# 01_-_MCU.net
KiCad netlist of a schematic drawn in Altium Designer
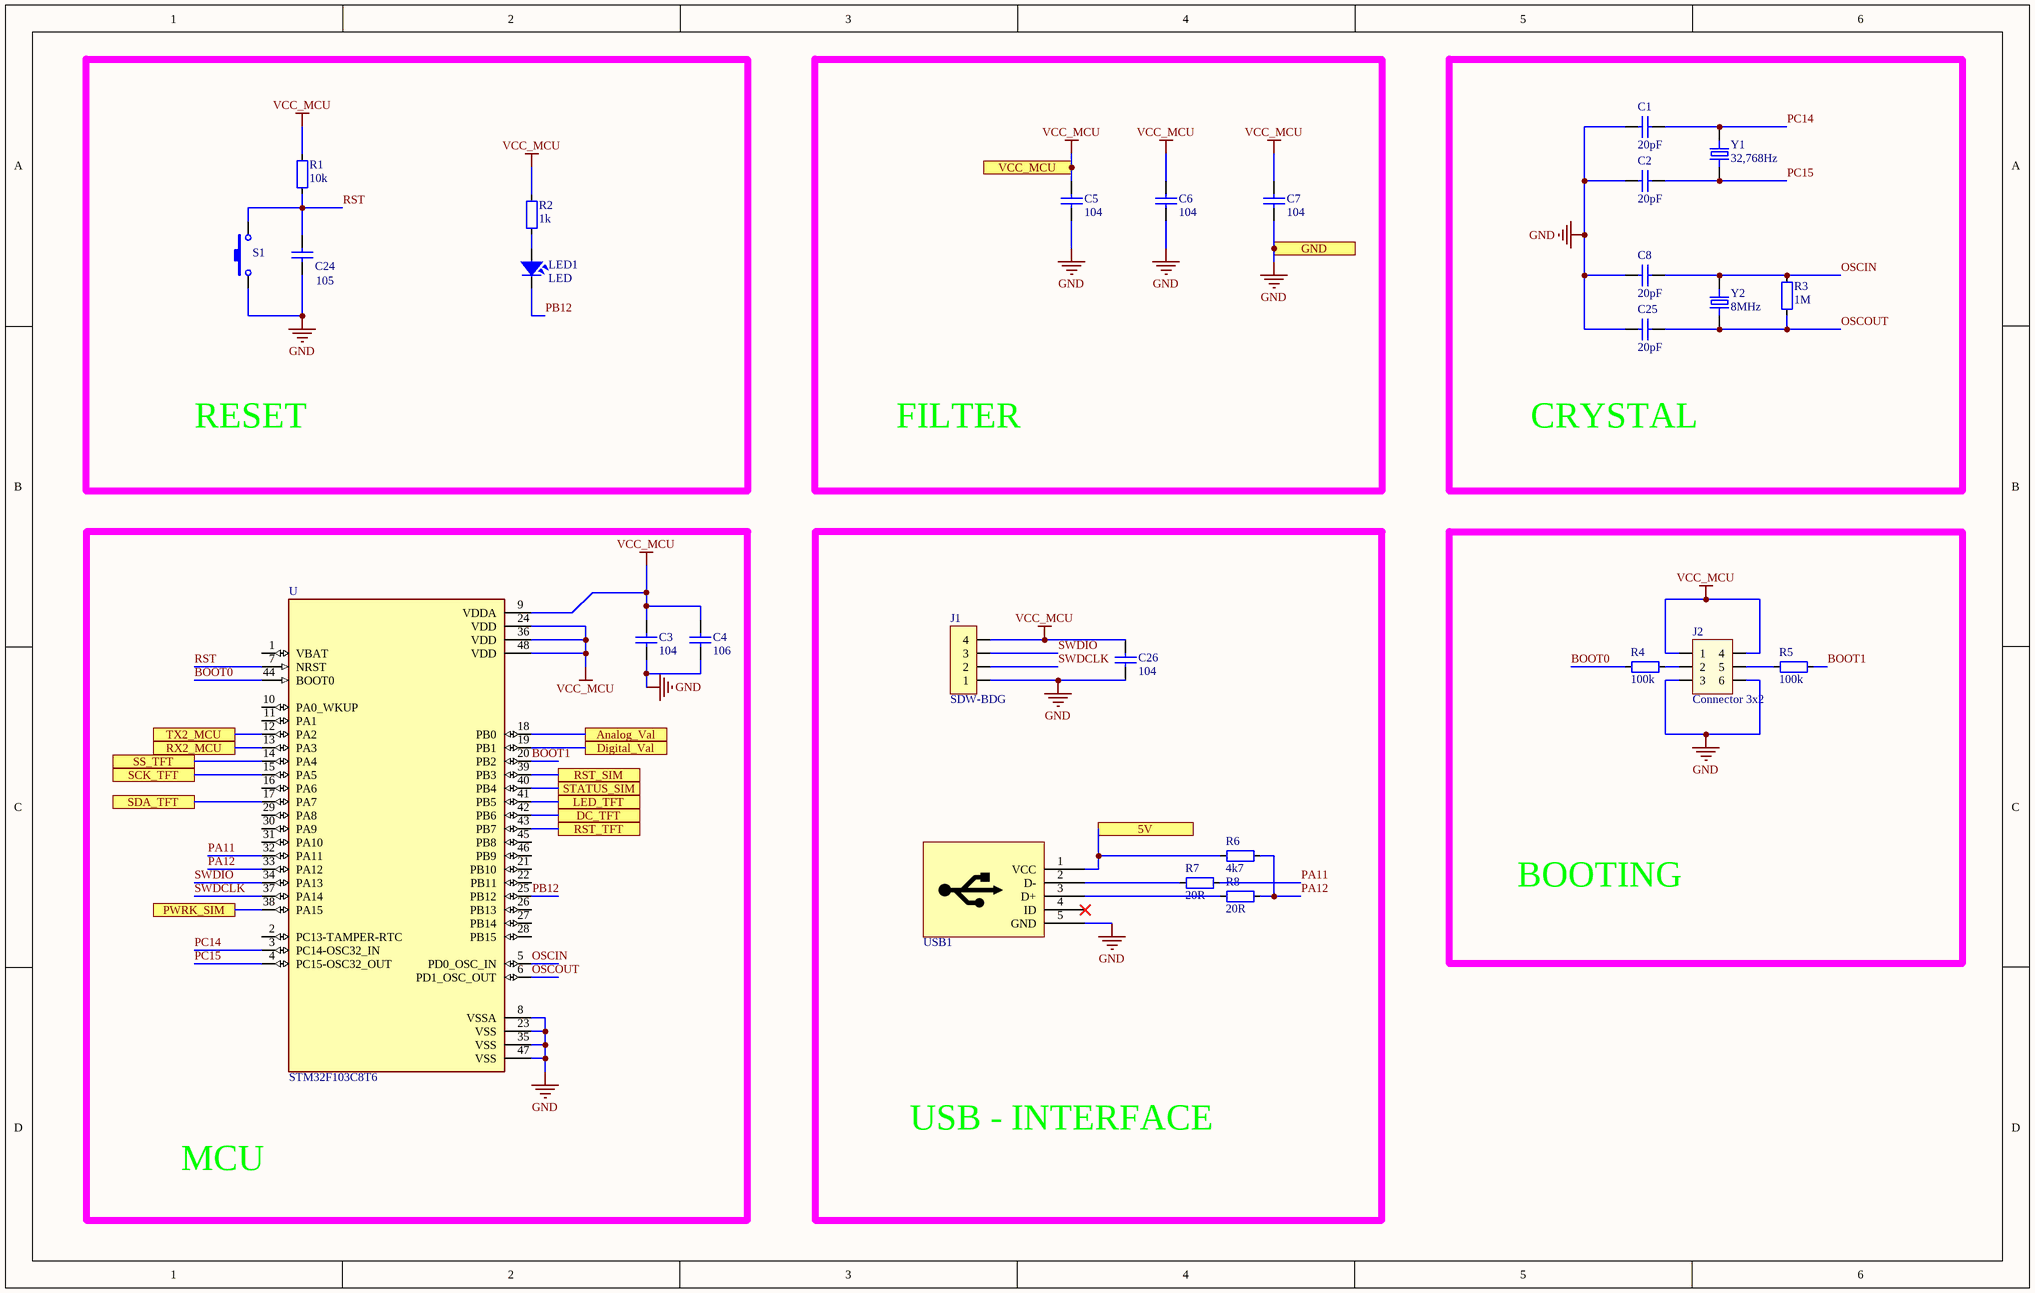
[diagram p0: [01] - MCU.SchDoc]

(export (version "E")
  (design (tool "Eeschema 10.0.6"))
  (components
    (comp (ref "C1")
      (value "20pF")
      (footprint "CAP_0805")
      (description "Capacitor")
      (fields (field (name "PUBLISHER") "Altium Limited"))
      (libsource (lib "HS_Lib") (part "CapSMD"))
    )
    (comp (ref "C2")
      (value "20pF")
      (footprint "CAP_0805")
      (description "Capacitor")
      (fields (field (name "PUBLISHER") "Altium Limited"))
      (libsource (lib "HS_Lib") (part "CapSMD"))
    )
    (comp (ref "C3")
      (value "104")
      (footprint "CAP_0603")
      (description "Capacitor")
      (fields (field (name "PUBLISHER") "Altium Limited"))
      (libsource (lib "HS_Lib") (part "CapSMD"))
    )
    (comp (ref "C4")
      (value "106")
      (footprint "CAP_1206")
      (description "Capacitor")
      (fields (field (name "PUBLISHER") "Altium Limited"))
      (libsource (lib "HS_Lib") (part "CapSMD"))
    )
    (comp (ref "C5")
      (value "104")
      (footprint "CAP_0603")
      (description "Capacitor")
      (fields (field (name "PUBLISHER") "Altium Limited"))
      (libsource (lib "HS_Lib") (part "CapSMD"))
    )
    (comp (ref "C6")
      (value "104")
      (footprint "CAP_0603")
      (description "Capacitor")
      (fields (field (name "PUBLISHER") "Altium Limited"))
      (libsource (lib "HS_Lib") (part "CapSMD"))
    )
    (comp (ref "C7")
      (value "104")
      (footprint "CAP_0603")
      (description "Capacitor")
      (fields (field (name "PUBLISHER") "Altium Limited"))
      (libsource (lib "HS_Lib") (part "CapSMD"))
    )
    (comp (ref "C8")
      (value "20pF")
      (footprint "CAP_0805")
      (description "Capacitor")
      (fields (field (name "PUBLISHER") "Altium Limited"))
      (libsource (lib "HS_Lib") (part "CapSMD"))
    )
    (comp (ref "C24")
      (value "105")
      (footprint "CAP_0603")
      (description "Capacitor")
      (fields (field (name "PUBLISHER") "Altium Limited"))
      (libsource (lib "HS_Lib") (part "CapSMD"))
    )
    (comp (ref "C25")
      (value "20pF")
      (footprint "CAP_0805")
      (description "Capacitor")
      (fields (field (name "PUBLISHER") "Altium Limited"))
      (libsource (lib "HS_Lib") (part "CapSMD"))
    )
    (comp (ref "C26")
      (value "104")
      (footprint "CAP_0603")
      (description "Capacitor")
      (fields (field (name "PUBLISHER") "Altium Limited"))
      (libsource (lib "HS_Lib") (part "CapSMD"))
    )
    (comp (ref "J1")
      (value "SDW-BDG")
      (footprint "JP4-D1C")
      (description "WR-PHD 2.54 mm Angled Socket Header")
      (fields
        (field (name "MANUFACTURER") "Würth Elektronik eiSos GmbH")
        (field (name "PARTNO") "613004143121")
        (field (name "CREATED BY") "Karrer Zheng")
      )
      (libsource (lib "HS_Lib") (part "JP4"))
    )
    (comp (ref "J2") (value "Connector 3x2") (footprint "JP3x2") (libsource (lib "HS_Lib") (part "JP3x2")))
    (comp (ref "LED1")
      (value "LED")
      (footprint "LED-0805-Red")
      (description "LED Single colour Green and Red")
      (libsource (lib "HS_Lib") (part "LED"))
    )
    (comp (ref "R1")
      (value "10k")
      (footprint "RES-SMD-0603")
      (description "Resistor")
      (fields
        (field (name "MANUFACTURER") "Generic Components")
        (field (name "PUBLISHER") "Altium Hobart Technology Centre")
      )
      (libsource (lib "HS_Lib") (part "Resistor - SMD"))
    )
    (comp (ref "R2")
      (value "1k")
      (footprint "RES-SMD-0603")
      (description "Resistor")
      (fields
        (field (name "MANUFACTURER") "Generic Components")
        (field (name "PUBLISHER") "Altium Hobart Technology Centre")
      )
      (libsource (lib "HS_Lib") (part "Resistor - SMD"))
    )
    (comp (ref "R3")
      (value "1M")
      (footprint "RES-SMD-0603")
      (description "Resistor")
      (fields
        (field (name "MANUFACTURER") "Generic Components")
        (field (name "PUBLISHER") "Altium Hobart Technology Centre")
      )
      (libsource (lib "HS_Lib") (part "Resistor - SMD"))
    )
    (comp (ref "R4")
      (value "100k")
      (footprint "RES-SMD-0603")
      (description "Resistor")
      (fields
        (field (name "MANUFACTURER") "Generic Components")
        (field (name "PUBLISHER") "Altium Hobart Technology Centre")
      )
      (libsource (lib "HS_Lib") (part "Resistor - SMD"))
    )
    (comp (ref "R5")
      (value "100k")
      (footprint "RES-SMD-0603")
      (description "Resistor")
      (fields
        (field (name "MANUFACTURER") "Generic Components")
        (field (name "PUBLISHER") "Altium Hobart Technology Centre")
      )
      (libsource (lib "HS_Lib") (part "Resistor - SMD"))
    )
    (comp (ref "R6")
      (value "4k7")
      (footprint "RES-SMD-0603")
      (description "Resistor")
      (fields
        (field (name "MANUFACTURER") "Generic Components")
        (field (name "PUBLISHER") "Altium Hobart Technology Centre")
      )
      (libsource (lib "HS_Lib") (part "Resistor - SMD"))
    )
    (comp (ref "R7")
      (value "20R")
      (footprint "RES-SMD-0603")
      (description "Resistor")
      (fields
        (field (name "MANUFACTURER") "Generic Components")
        (field (name "PUBLISHER") "Altium Hobart Technology Centre")
      )
      (libsource (lib "HS_Lib") (part "Resistor - SMD"))
    )
    (comp (ref "R8")
      (value "20R")
      (footprint "RES-SMD-0603")
      (description "Resistor")
      (fields
        (field (name "MANUFACTURER") "Generic Components")
        (field (name "PUBLISHER") "Altium Hobart Technology Centre")
      )
      (libsource (lib "HS_Lib") (part "Resistor - SMD"))
    )
    (comp (ref "S1")
      (value "SW-SMD")
      (footprint "SW 3x2x4")
      (description "Switch")
      (fields (field (name "PUBLISHER") "Altium Limited"))
      (libsource (lib "HS_Lib") (part "SW-SMD"))
    )
    (comp (ref "U")
      (value "STM32F103C8T6")
      (footprint "STM32F103C8T6")
      (description "ARMÂ® CortexÂ®-M3 STM32F1 Microcontroller IC 32-Bit 72MHz 64KB _64K x 8_ FLASH")
      (fields (field (name "MF") "STMicroelectronics"))
      (libsource (lib "HS_Lib") (part "STM32F103C8T6"))
    )
    (comp (ref "USB1") (value "USB") (footprint "USB-M1") (libsource (lib "HS_Lib") (part "USB-micro")))
    (comp (ref "Y1")
      (value "32,768Hz")
      (footprint "XTAL_ABLS-20.000MHZ-B4-T")
      (description "8MHz Â±20ppm Crystal 18pF 80 Ohms HC-49/US")
      (fields (field (name "MP") "ABLS-8.000MHZ-B2") (field (name "MF") "Abracon LLC"))
      (libsource (lib "HS_Lib") (part "Crystal"))
    )
    (comp (ref "Y2")
      (value "8MHz")
      (footprint "XTAL_ABLS-20.000MHZ-B4-T")
      (description "8MHz Â±20ppm Crystal 18pF 80 Ohms HC-49/US")
      (fields (field (name "MP") "ABLS-8.000MHZ-B2") (field (name "MF") "Abracon LLC"))
      (libsource (lib "HS_Lib") (part "Crystal"))
    )
  )
  (nets
    (net (code "1") (name "/5V") (class "Default")
      (node (ref "R6") (pin "2") (pinfunction "2_2") (pintype "passive"))
      (node (ref "USB1") (pin "1") (pinfunction "VCC_1") (pintype "passive"))
    )
    (net (code "2") (name "/Analog_Val") (class "Default")
      (node (ref "U") (pin "18") (pinfunction "PB0_18") (pintype "bidirectional"))
    )
    (net (code "3") (name "/BOOT0") (class "Default")
      (node (ref "R4") (pin "1") (pinfunction "1_1") (pintype "passive"))
      (node (ref "U") (pin "44") (pinfunction "BOOT0_44") (pintype "input"))
    )
    (net (code "4") (name "/BOOT1") (class "Default")
      (node (ref "R5") (pin "2") (pinfunction "2_2") (pintype "passive"))
      (node (ref "U") (pin "20") (pinfunction "PB2_20") (pintype "bidirectional"))
    )
    (net (code "5") (name "/DC_TFT") (class "Default")
      (node (ref "U") (pin "42") (pinfunction "PB6_42") (pintype "bidirectional"))
    )
    (net (code "6") (name "/Digital_Val") (class "Default")
      (node (ref "U") (pin "19") (pinfunction "PB1_19") (pintype "bidirectional"))
    )
    (net (code "7") (name "/LED_TFT") (class "Default")
      (node (ref "U") (pin "41") (pinfunction "PB5_41") (pintype "bidirectional"))
    )
    (net (code "8") (name "/OSCIN") (class "Default")
      (node (ref "C8") (pin "2") (pinfunction "2_2") (pintype "passive"))
      (node (ref "R3") (pin "2") (pinfunction "2_2") (pintype "passive"))
      (node (ref "U") (pin "5") (pinfunction "PD0_OSC_IN_5") (pintype "bidirectional"))
      (node (ref "Y2") (pin "2") (pinfunction "2_2") (pintype "passive"))
    )
    (net (code "9") (name "/OSCOUT") (class "Default")
      (node (ref "C25") (pin "2") (pinfunction "2_2") (pintype "passive"))
      (node (ref "R3") (pin "1") (pinfunction "1_1") (pintype "passive"))
      (node (ref "U") (pin "6") (pinfunction "PD1_OSC_OUT_6") (pintype "bidirectional"))
      (node (ref "Y2") (pin "1") (pinfunction "1_1") (pintype "passive"))
    )
    (net (code "10") (name "/PA11") (class "Default")
      (node (ref "R7") (pin "2") (pinfunction "2_2") (pintype "passive"))
      (node (ref "U") (pin "32") (pinfunction "PA11_32") (pintype "bidirectional"))
    )
    (net (code "11") (name "/PA12") (class "Default")
      (node (ref "R6") (pin "1") (pinfunction "1_1") (pintype "passive"))
      (node (ref "R8") (pin "2") (pinfunction "2_2") (pintype "passive"))
      (node (ref "U") (pin "33") (pinfunction "PA12_33") (pintype "bidirectional"))
    )
    (net (code "12") (name "/PB12") (class "Default")
      (node (ref "LED1") (pin "2") (pinfunction "2_2") (pintype "passive"))
      (node (ref "U") (pin "25") (pinfunction "PB12_25") (pintype "bidirectional"))
    )
    (net (code "13") (name "/PC14") (class "Default")
      (node (ref "C1") (pin "2") (pinfunction "2_2") (pintype "passive"))
      (node (ref "U") (pin "3") (pinfunction "PC14-OSC32_IN_3") (pintype "bidirectional"))
      (node (ref "Y1") (pin "2") (pinfunction "2_2") (pintype "passive"))
    )
    (net (code "14") (name "/PC15") (class "Default")
      (node (ref "C2") (pin "2") (pinfunction "2_2") (pintype "passive"))
      (node (ref "U") (pin "4") (pinfunction "PC15-OSC32_OUT_4") (pintype "bidirectional"))
      (node (ref "Y1") (pin "1") (pinfunction "1_1") (pintype "passive"))
    )
    (net (code "15") (name "/PWRK_SIM") (class "Default")
      (node (ref "U") (pin "38") (pinfunction "PA15_38") (pintype "bidirectional"))
    )
    (net (code "16") (name "/RST") (class "Default")
      (node (ref "C24") (pin "2") (pinfunction "2_2") (pintype "passive"))
      (node (ref "R1") (pin "1") (pinfunction "1_1") (pintype "passive"))
      (node (ref "S1") (pin "2") (pinfunction "2_2") (pintype "passive"))
      (node (ref "U") (pin "7") (pinfunction "NRST_7") (pintype "input"))
    )
    (net (code "17") (name "/RST_SIM") (class "Default")
      (node (ref "U") (pin "39") (pinfunction "PB3_39") (pintype "bidirectional"))
    )
    (net (code "18") (name "/RST_TFT") (class "Default")
      (node (ref "U") (pin "43") (pinfunction "PB7_43") (pintype "bidirectional"))
    )
    (net (code "19") (name "/RX2_MCU") (class "Default")
      (node (ref "U") (pin "13") (pinfunction "PA3_13") (pintype "bidirectional"))
    )
    (net (code "20") (name "/SCK_TFT") (class "Default")
      (node (ref "U") (pin "15") (pinfunction "PA5_15") (pintype "bidirectional"))
    )
    (net (code "21") (name "/SDA_TFT") (class "Default")
      (node (ref "U") (pin "17") (pinfunction "PA7_17") (pintype "bidirectional"))
    )
    (net (code "22") (name "/SS_TFT") (class "Default")
      (node (ref "U") (pin "14") (pinfunction "PA4_14") (pintype "bidirectional"))
    )
    (net (code "23") (name "/STATUS_SIM") (class "Default")
      (node (ref "U") (pin "40") (pinfunction "PB4_40") (pintype "bidirectional"))
    )
    (net (code "24") (name "/SWDCLK") (class "Default")
      (node (ref "J1") (pin "2") (pinfunction "2_2") (pintype "passive"))
      (node (ref "U") (pin "37") (pinfunction "PA14_37") (pintype "bidirectional"))
    )
    (net (code "25") (name "/SWDIO") (class "Default")
      (node (ref "J1") (pin "3") (pinfunction "3_3") (pintype "passive"))
      (node (ref "U") (pin "34") (pinfunction "PA13_34") (pintype "bidirectional"))
    )
    (net (code "26") (name "/TX2_MCU") (class "Default")
      (node (ref "U") (pin "12") (pinfunction "PA2_12") (pintype "bidirectional"))
    )
    (net (code "27") (name "GND") (class "Default")
      (node (ref "C1") (pin "1") (pinfunction "1_1") (pintype "passive"))
      (node (ref "C2") (pin "1") (pinfunction "1_1") (pintype "passive"))
      (node (ref "C24") (pin "1") (pinfunction "1_1") (pintype "passive"))
      (node (ref "C25") (pin "1") (pinfunction "1_1") (pintype "passive"))
      (node (ref "C26") (pin "1") (pinfunction "1_1") (pintype "passive"))
      (node (ref "C3") (pin "1") (pinfunction "1_1") (pintype "passive"))
      (node (ref "C4") (pin "1") (pinfunction "1_1") (pintype "passive"))
      (node (ref "C5") (pin "1") (pinfunction "1_1") (pintype "passive"))
      (node (ref "C6") (pin "1") (pinfunction "1_1") (pintype "passive"))
      (node (ref "C7") (pin "1") (pinfunction "1_1") (pintype "passive"))
      (node (ref "C8") (pin "1") (pinfunction "1_1") (pintype "passive"))
      (node (ref "J1") (pin "1") (pinfunction "1_1") (pintype "passive"))
      (node (ref "J2") (pin "3") (pinfunction "3_3") (pintype "passive"))
      (node (ref "J2") (pin "6") (pinfunction "6_6") (pintype "passive"))
      (node (ref "S1") (pin "1") (pinfunction "1_1") (pintype "passive"))
      (node (ref "U") (pin "23") (pinfunction "VSS_23") (pintype "power_in"))
      (node (ref "U") (pin "35") (pinfunction "VSS_35") (pintype "power_in"))
      (node (ref "U") (pin "47") (pinfunction "VSS_47") (pintype "power_in"))
      (node (ref "U") (pin "8") (pinfunction "VSSA_8") (pintype "power_in"))
      (node (ref "USB1") (pin "5") (pinfunction "GND_5") (pintype "passive"))
    )
    (net (code "28") (name "Net-(J2-Pad2)") (class "Default")
      (node (ref "J2") (pin "2") (pinfunction "2_2") (pintype "passive"))
      (node (ref "R4") (pin "2") (pinfunction "2_2") (pintype "passive"))
    )
    (net (code "29") (name "Net-(J2-Pad5)") (class "Default")
      (node (ref "J2") (pin "5") (pinfunction "5_5") (pintype "passive"))
      (node (ref "R5") (pin "1") (pinfunction "1_1") (pintype "passive"))
    )
    (net (code "30") (name "Net-(LED1-Pad1)") (class "Default")
      (node (ref "LED1") (pin "1") (pinfunction "1_1") (pintype "passive"))
      (node (ref "R2") (pin "1") (pinfunction "1_1") (pintype "passive"))
    )
    (net (code "31") (name "Net-(USB1-D+)") (class "Default")
      (node (ref "R8") (pin "1") (pinfunction "1_1") (pintype "passive"))
      (node (ref "USB1") (pin "3") (pinfunction "D+_3") (pintype "passive"))
    )
    (net (code "32") (name "Net-(USB1-D-)") (class "Default")
      (node (ref "R7") (pin "1") (pinfunction "1_1") (pintype "passive"))
      (node (ref "USB1") (pin "2") (pinfunction "D-_2") (pintype "passive"))
    )
    (net (code "33") (name "VCC_MCU") (class "Default")
      (node (ref "C26") (pin "2") (pinfunction "2_2") (pintype "passive"))
      (node (ref "C3") (pin "2") (pinfunction "2_2") (pintype "passive"))
      (node (ref "C4") (pin "2") (pinfunction "2_2") (pintype "passive"))
      (node (ref "C5") (pin "2") (pinfunction "2_2") (pintype "passive"))
      (node (ref "C6") (pin "2") (pinfunction "2_2") (pintype "passive"))
      (node (ref "C7") (pin "2") (pinfunction "2_2") (pintype "passive"))
      (node (ref "J1") (pin "4") (pinfunction "4_4") (pintype "passive"))
      (node (ref "J2") (pin "1") (pinfunction "1_1") (pintype "passive"))
      (node (ref "J2") (pin "4") (pinfunction "4_4") (pintype "passive"))
      (node (ref "R1") (pin "2") (pinfunction "2_2") (pintype "passive"))
      (node (ref "R2") (pin "2") (pinfunction "2_2") (pintype "passive"))
      (node (ref "U") (pin "24") (pinfunction "VDD_24") (pintype "power_in"))
      (node (ref "U") (pin "36") (pinfunction "VDD_36") (pintype "power_in"))
      (node (ref "U") (pin "48") (pinfunction "VDD_48") (pintype "power_in"))
      (node (ref "U") (pin "9") (pinfunction "VDDA_9") (pintype "power_in"))
    )
    (net (code "34") (name "unconnected-(U-PA0_WKUP-Pad10)") (class "Default")
      (node (ref "U") (pin "10") (pinfunction "PA0_WKUP_10") (pintype "bidirectional"))
    )
    (net (code "35") (name "unconnected-(U-PA1-Pad11)") (class "Default")
      (node (ref "U") (pin "11") (pinfunction "PA1_11") (pintype "bidirectional"))
    )
    (net (code "36") (name "unconnected-(U-PA6-Pad16)") (class "Default")
      (node (ref "U") (pin "16") (pinfunction "PA6_16") (pintype "bidirectional"))
    )
    (net (code "37") (name "unconnected-(U-PA8-Pad29)") (class "Default")
      (node (ref "U") (pin "29") (pinfunction "PA8_29") (pintype "bidirectional"))
    )
    (net (code "38") (name "unconnected-(U-PA9-Pad30)") (class "Default")
      (node (ref "U") (pin "30") (pinfunction "PA9_30") (pintype "bidirectional"))
    )
    (net (code "39") (name "unconnected-(U-PA10-Pad31)") (class "Default")
      (node (ref "U") (pin "31") (pinfunction "PA10_31") (pintype "bidirectional"))
    )
    (net (code "40") (name "unconnected-(U-PB8-Pad45)") (class "Default")
      (node (ref "U") (pin "45") (pinfunction "PB8_45") (pintype "bidirectional"))
    )
    (net (code "41") (name "unconnected-(U-PB9-Pad46)") (class "Default")
      (node (ref "U") (pin "46") (pinfunction "PB9_46") (pintype "bidirectional"))
    )
    (net (code "42") (name "unconnected-(U-PB10-Pad21)") (class "Default")
      (node (ref "U") (pin "21") (pinfunction "PB10_21") (pintype "bidirectional"))
    )
    (net (code "43") (name "unconnected-(U-PB11-Pad22)") (class "Default")
      (node (ref "U") (pin "22") (pinfunction "PB11_22") (pintype "bidirectional"))
    )
    (net (code "44") (name "unconnected-(U-PB13-Pad26)") (class "Default")
      (node (ref "U") (pin "26") (pinfunction "PB13_26") (pintype "bidirectional"))
    )
    (net (code "45") (name "unconnected-(U-PB14-Pad27)") (class "Default")
      (node (ref "U") (pin "27") (pinfunction "PB14_27") (pintype "bidirectional"))
    )
    (net (code "46") (name "unconnected-(U-PB15-Pad28)") (class "Default")
      (node (ref "U") (pin "28") (pinfunction "PB15_28") (pintype "bidirectional"))
    )
    (net (code "47") (name "unconnected-(U-PC13-TAMPER-RTC-Pad2)") (class "Default")
      (node (ref "U") (pin "2") (pinfunction "PC13-TAMPER-RTC_2") (pintype "bidirectional"))
    )
    (net (code "48") (name "unconnected-(U-VBAT-Pad1)") (class "Default")
      (node (ref "U") (pin "1") (pinfunction "VBAT_1") (pintype "bidirectional"))
    )
    (net (code "49") (name "unconnected-(USB1-ID-Pad4)") (class "Default")
      (node (ref "USB1") (pin "4") (pinfunction "ID_4") (pintype "passive+no_connect"))
    )
  )
)
